# Sheet1.net
KiCad netlist of a schematic drawn in Altium Designer
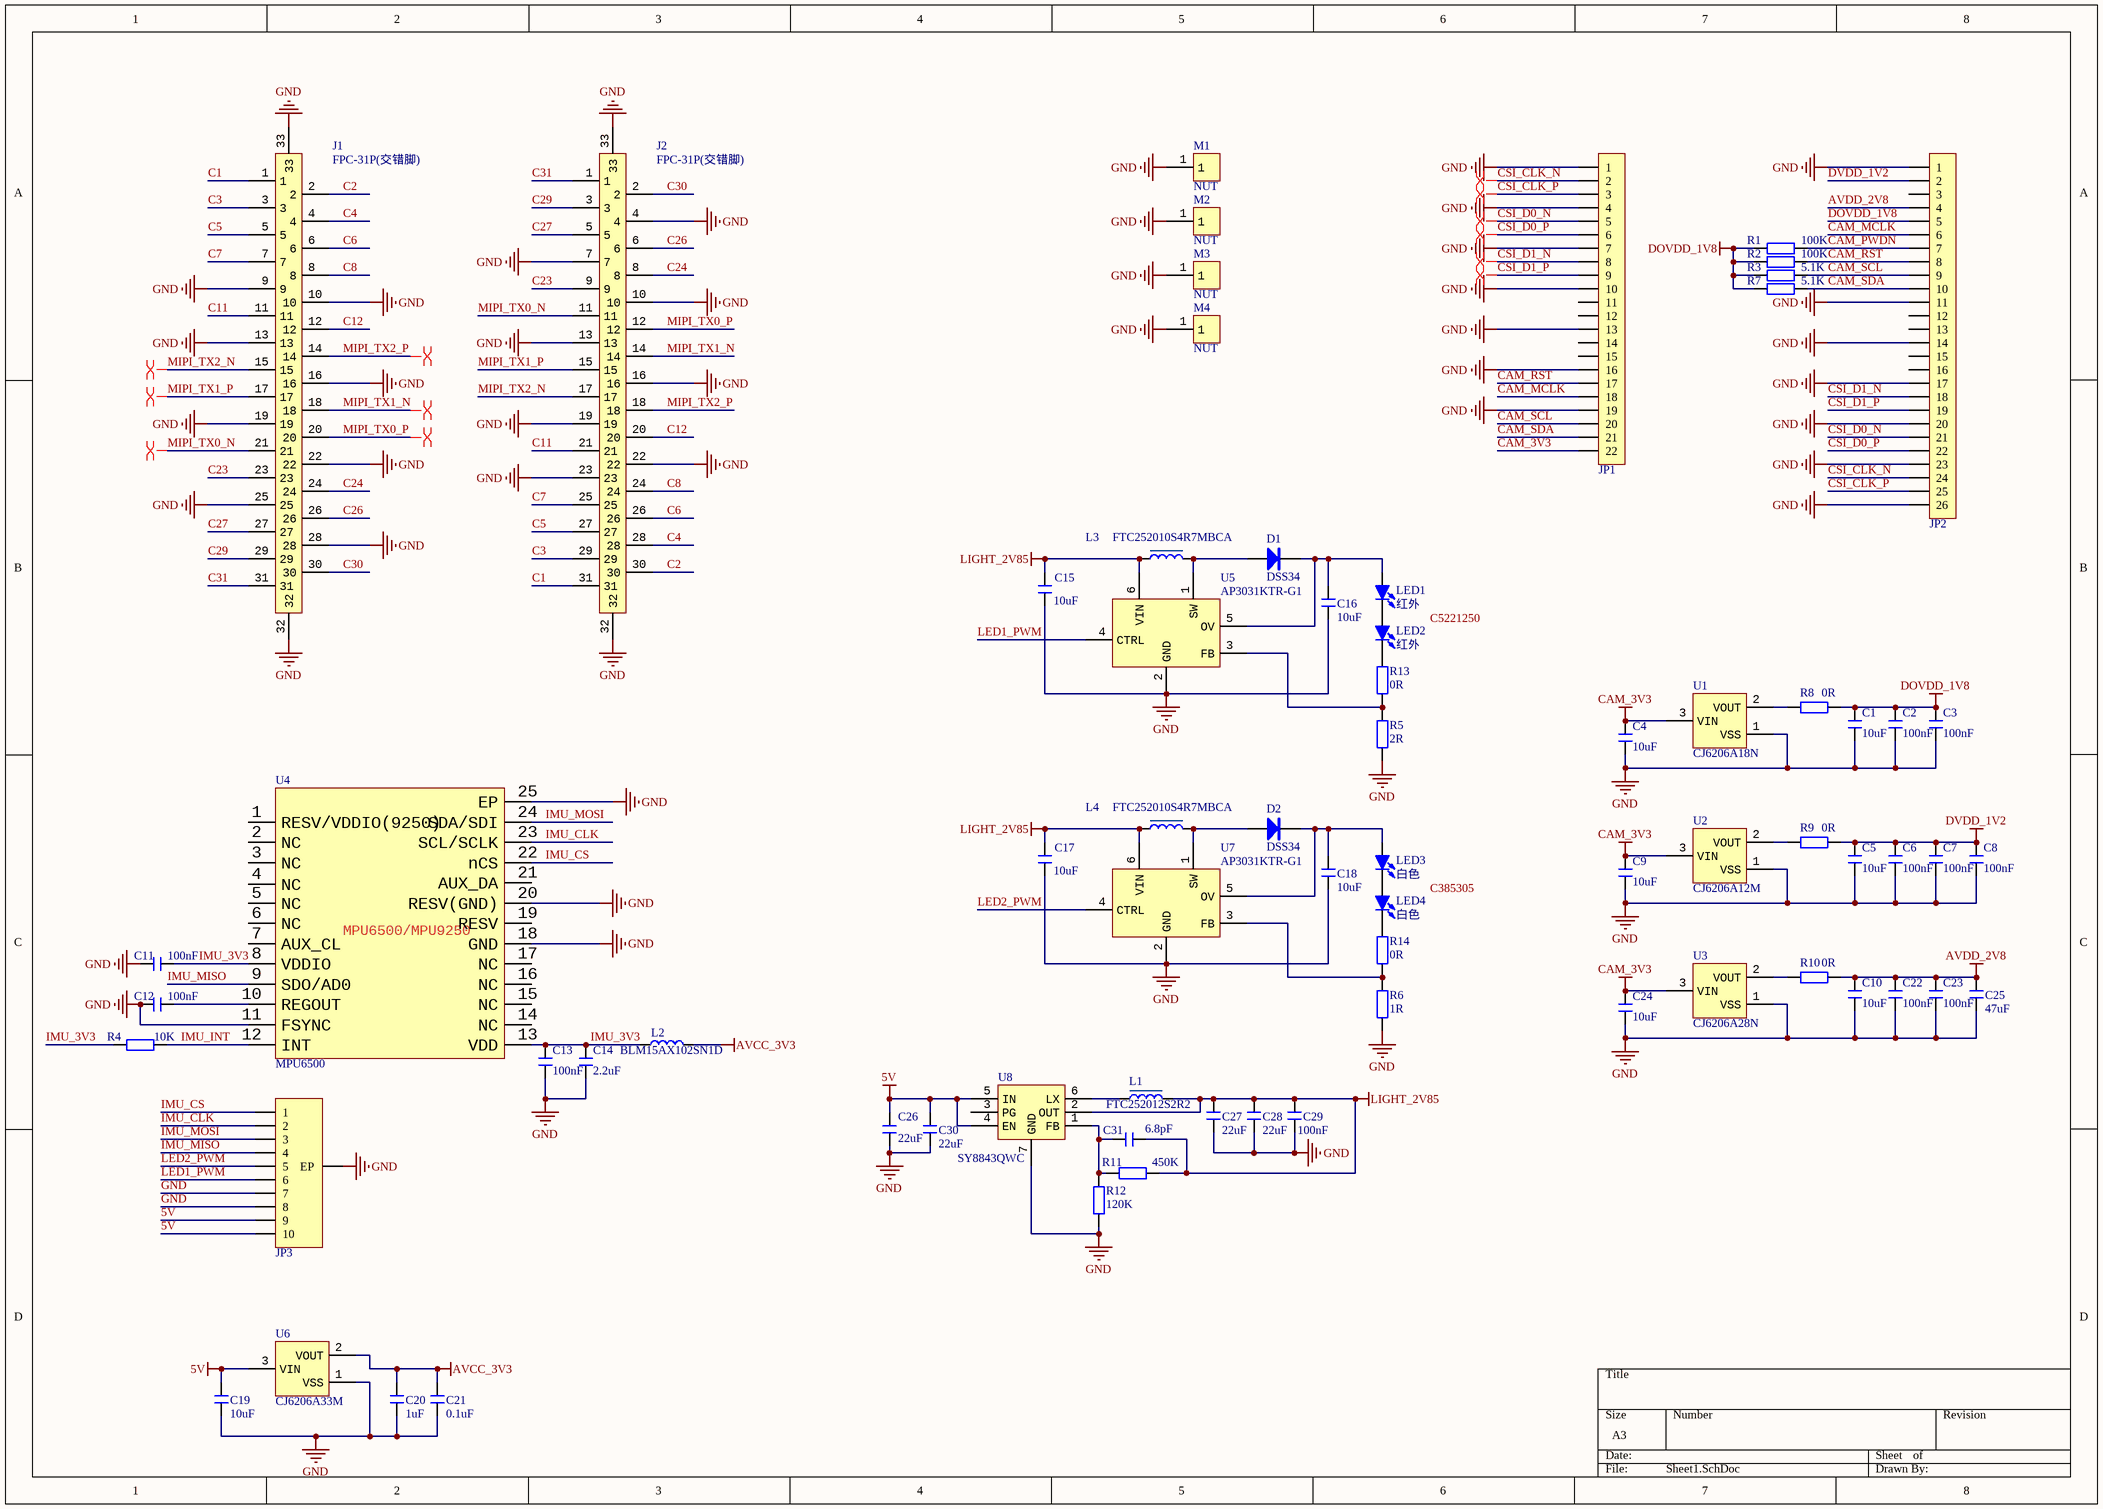
[diagram p0: Sheet1.SchDoc]

(export (version "E")
  (design (tool "Eeschema 10.0.6"))
  (components
    (comp (ref "C1")
      (value "10uF")
      (footprint "C 0402_L")
      (description "无极性贴片电容")
      (fields (field (name "版权归属") "源创客"))
      (libsource (lib "3.1   - 电阻-电容-电感") (part "C"))
    )
    (comp (ref "C2")
      (value "100nF")
      (footprint "C 0402_L")
      (description "无极性贴片电容")
      (fields (field (name "版权归属") "源创客"))
      (libsource (lib "3.1   - 电阻-电容-电感") (part "C"))
    )
    (comp (ref "C3")
      (value "100nF")
      (footprint "C 0402_L")
      (description "无极性贴片电容")
      (fields (field (name "版权归属") "源创客"))
      (libsource (lib "3.1   - 电阻-电容-电感") (part "C"))
    )
    (comp (ref "C4")
      (value "10uF")
      (footprint "C 0402_L")
      (description "无极性贴片电容")
      (fields (field (name "版权归属") "源创客"))
      (libsource (lib "3.1   - 电阻-电容-电感") (part "C"))
    )
    (comp (ref "C5")
      (value "10uF")
      (footprint "C 0402_L")
      (description "无极性贴片电容")
      (fields (field (name "版权归属") "源创客"))
      (libsource (lib "3.1   - 电阻-电容-电感") (part "C"))
    )
    (comp (ref "C6")
      (value "100nF")
      (footprint "C 0402_L")
      (description "无极性贴片电容")
      (fields (field (name "版权归属") "源创客"))
      (libsource (lib "3.1   - 电阻-电容-电感") (part "C"))
    )
    (comp (ref "C7")
      (value "100nF")
      (footprint "C 0402_L")
      (description "无极性贴片电容")
      (fields (field (name "版权归属") "源创客"))
      (libsource (lib "3.1   - 电阻-电容-电感") (part "C"))
    )
    (comp (ref "C8")
      (value "100nF")
      (footprint "C 0402_L")
      (description "无极性贴片电容")
      (fields (field (name "版权归属") "源创客"))
      (libsource (lib "3.1   - 电阻-电容-电感") (part "C"))
    )
    (comp (ref "C9")
      (value "10uF")
      (footprint "C 0402_L")
      (description "无极性贴片电容")
      (fields (field (name "版权归属") "源创客"))
      (libsource (lib "3.1   - 电阻-电容-电感") (part "C"))
    )
    (comp (ref "C10")
      (value "10uF")
      (footprint "C 0402_L")
      (description "无极性贴片电容")
      (fields (field (name "版权归属") "源创客"))
      (libsource (lib "3.1   - 电阻-电容-电感") (part "C"))
    )
    (comp (ref "C11")
      (value "100nF")
      (footprint "C 0402_L")
      (description "无极性贴片电容")
      (fields (field (name "版权归属") "源创客"))
      (libsource (lib "3.1   - 电阻-电容-电感") (part "C"))
    )
    (comp (ref "C12")
      (value "100nF")
      (footprint "C 0402_L")
      (description "无极性贴片电容")
      (fields (field (name "版权归属") "源创客"))
      (libsource (lib "3.1   - 电阻-电容-电感") (part "C"))
    )
    (comp (ref "C13")
      (value "100nF")
      (footprint "C 0402_L")
      (description "无极性贴片电容")
      (fields (field (name "版权归属") "源创客"))
      (libsource (lib "3.1   - 电阻-电容-电感") (part "C"))
    )
    (comp (ref "C14")
      (value "2.2uF")
      (footprint "C 0402_L")
      (description "无极性贴片电容")
      (fields (field (name "版权归属") "源创客"))
      (libsource (lib "3.1   - 电阻-电容-电感") (part "C"))
    )
    (comp (ref "C15")
      (value "10uF")
      (footprint "C 0603_L")
      (description "无极性贴片电容")
      (fields (field (name "版权归属") "源创客"))
      (libsource (lib "3.1   - 电阻-电容-电感") (part "C"))
    )
    (comp (ref "C16")
      (value "10uF")
      (footprint "C 0603_L")
      (description "无极性贴片电容")
      (fields (field (name "版权归属") "源创客"))
      (libsource (lib "3.1   - 电阻-电容-电感") (part "C"))
    )
    (comp (ref "C17")
      (value "10uF")
      (footprint "C 0603_L")
      (description "无极性贴片电容")
      (fields (field (name "版权归属") "源创客"))
      (libsource (lib "3.1   - 电阻-电容-电感") (part "C"))
    )
    (comp (ref "C18")
      (value "10uF")
      (footprint "C 0603_L")
      (description "无极性贴片电容")
      (fields (field (name "版权归属") "源创客"))
      (libsource (lib "3.1   - 电阻-电容-电感") (part "C"))
    )
    (comp (ref "C19")
      (value "10uF")
      (footprint "C 0603_L")
      (description "无极性贴片电容")
      (fields (field (name "版权归属") "源创客"))
      (libsource (lib "3.1   - 电阻-电容-电感") (part "C"))
    )
    (comp (ref "C20")
      (value "1uF")
      (footprint "C 0402_L")
      (description "无极性贴片电容")
      (fields (field (name "版权归属") "源创客"))
      (libsource (lib "3.1   - 电阻-电容-电感") (part "C"))
    )
    (comp (ref "C21")
      (value "0.1uF")
      (footprint "C 0402_L")
      (description "无极性贴片电容")
      (fields (field (name "版权归属") "源创客"))
      (libsource (lib "3.1   - 电阻-电容-电感") (part "C"))
    )
    (comp (ref "C22")
      (value "100nF")
      (footprint "C 0402_L")
      (description "无极性贴片电容")
      (fields (field (name "版权归属") "源创客"))
      (libsource (lib "3.1   - 电阻-电容-电感") (part "C"))
    )
    (comp (ref "C23")
      (value "100nF")
      (footprint "C 0402_L")
      (description "无极性贴片电容")
      (fields (field (name "版权归属") "源创客"))
      (libsource (lib "3.1   - 电阻-电容-电感") (part "C"))
    )
    (comp (ref "C24")
      (value "10uF")
      (footprint "C 0402_L")
      (description "无极性贴片电容")
      (fields (field (name "版权归属") "源创客"))
      (libsource (lib "3.1   - 电阻-电容-电感") (part "C"))
    )
    (comp (ref "C25")
      (value "47uF")
      (footprint "C 0603_L")
      (description "无极性贴片电容")
      (fields (field (name "版权归属") "源创客"))
      (libsource (lib "3.1   - 电阻-电容-电感") (part "C"))
    )
    (comp (ref "C26")
      (value "22uF")
      (footprint "C 0603_L")
      (description "无极性贴片电容")
      (fields (field (name "版权归属") "源创客"))
      (libsource (lib "3.1   - 电阻-电容-电感") (part "C"))
    )
    (comp (ref "C27")
      (value "22uF")
      (footprint "C 0603_L")
      (description "无极性贴片电容")
      (fields (field (name "版权归属") "源创客"))
      (libsource (lib "3.1   - 电阻-电容-电感") (part "C"))
    )
    (comp (ref "C28")
      (value "22uF")
      (footprint "C 0603_L")
      (description "无极性贴片电容")
      (fields (field (name "版权归属") "源创客"))
      (libsource (lib "3.1   - 电阻-电容-电感") (part "C"))
    )
    (comp (ref "C29")
      (value "100nF")
      (footprint "C 0402_L")
      (description "无极性贴片电容")
      (fields (field (name "版权归属") "源创客"))
      (libsource (lib "3.1   - 电阻-电容-电感") (part "C"))
    )
    (comp (ref "C30")
      (value "22uF")
      (footprint "C 0603_L")
      (description "无极性贴片电容")
      (fields (field (name "版权归属") "源创客"))
      (libsource (lib "3.1   - 电阻-电容-电感") (part "C"))
    )
    (comp (ref "C31")
      (value "6.8pF")
      (footprint "C 0402_L")
      (description "无极性贴片电容")
      (fields (field (name "版权归属") "源创客"))
      (libsource (lib "3.1   - 电阻-电容-电感") (part "C"))
    )
    (comp (ref "D1")
      (value "DSS34")
      (footprint "SOD-123FL")
      (description "肖特基二极管")
      (libsource (lib "8.1   - 二极管-整流桥") (part "DSS34"))
    )
    (comp (ref "D2")
      (value "DSS34")
      (footprint "SOD-123FL")
      (description "肖特基二极管")
      (libsource (lib "8.1   - 二极管-整流桥") (part "DSS34"))
    )
    (comp (ref "J1")
      (value "FPC-31P(交错脚)")
      (footprint "FPC 1H-WS-31P")
      (description "FPC连接器")
      (libsource (lib "4.14 - FPC连接器") (part "FPC-31P(交错脚)"))
    )
    (comp (ref "J2")
      (value "FPC-31P(交错脚)")
      (footprint "FPC 1H-WS-31P")
      (description "FPC连接器")
      (libsource (lib "4.14 - FPC连接器") (part "FPC-31P(交错脚)"))
    )
    (comp (ref "JP1")
      (value "FPC1.0-22P")
      (footprint "FPC0.5 2H-WS-22P")
      (description "FPC连接器")
      (fields (field (name "版权归属") "源创客"))
      (libsource (lib "4.14 - FPC连接器") (part "FPC-22P"))
    )
    (comp (ref "JP2")
      (value "FPC1.0-26P")
      (footprint "FPC0.5 2H-WS-26P")
      (description "FPC连接器")
      (fields (field (name "版权归属") "源创客"))
      (libsource (lib "4.14 - FPC连接器") (part "FPC-26P"))
    )
    (comp (ref "JP3")
      (value "FPC1.0-10P")
      (footprint "FPC0.5 1H-WS-10P")
      (description "FPC连接器")
      (fields (field (name "版权归属") "源创客"))
      (libsource (lib "4.14 - FPC连接器") (part "FPC-10P"))
    )
    (comp (ref "L1")
      (value "FTC252012S2R2")
      (footprint "252012")
      (description "贴片功率电感")
      (fields (field (name "版权归属") "源创客"))
      (libsource (lib "3.1   - 电阻-电容-电感") (part "L-CD"))
    )
    (comp (ref "L2")
      (value "BLM15AX102SN1D")
      (footprint "L 0402")
      (description "小功率贴片电感")
      (fields (field (name "版权归属") "源创客"))
      (libsource (lib "3.1   - 电阻-电容-电感") (part "L"))
    )
    (comp (ref "L3")
      (value "FTC252010S4R7MBCA")
      (footprint "252012")
      (description "贴片功率电感")
      (fields (field (name "版权归属") "源创客"))
      (libsource (lib "3.1   - 电阻-电容-电感") (part "L-CD"))
    )
    (comp (ref "L4")
      (value "FTC252010S4R7MBCA")
      (footprint "252012")
      (description "贴片功率电感")
      (fields (field (name "版权归属") "源创客"))
      (libsource (lib "3.1   - 电阻-电容-电感") (part "L-CD"))
    )
    (comp (ref "LED1")
      (value "红外")
      (footprint "LED 3528-2Pin")
      (description "贴片LED")
      (fields (field (name "版权归属") "源创客"))
      (libsource (lib "9.1   - LED") (part "LED-SMD"))
    )
    (comp (ref "LED2")
      (value "红外")
      (footprint "LED 3528-2Pin")
      (description "贴片LED")
      (fields (field (name "版权归属") "源创客"))
      (libsource (lib "9.1   - LED") (part "LED-SMD"))
    )
    (comp (ref "LED3")
      (value "白色")
      (footprint "LED 3528-2Pin")
      (description "贴片LED")
      (fields (field (name "版权归属") "源创客"))
      (libsource (lib "9.1   - LED") (part "LED-SMD"))
    )
    (comp (ref "LED4")
      (value "白色")
      (footprint "LED 3528-2Pin")
      (description "贴片LED")
      (fields (field (name "版权归属") "源创客"))
      (libsource (lib "9.1   - LED") (part "LED-SMD"))
    )
    (comp (ref "M1")
      (value "NUT")
      (footprint "SMT-NUT-M1610")
      (description "SMT表贴螺母")
      (libsource (lib "15.1 - 未分类器件") (part "SMTNUT"))
    )
    (comp (ref "M2")
      (value "NUT")
      (footprint "SMT-NUT-M1610")
      (description "SMT表贴螺母")
      (libsource (lib "15.1 - 未分类器件") (part "SMTNUT"))
    )
    (comp (ref "M3")
      (value "NUT")
      (footprint "SMT-NUT-M1610")
      (description "SMT表贴螺母")
      (libsource (lib "15.1 - 未分类器件") (part "SMTNUT"))
    )
    (comp (ref "M4")
      (value "NUT")
      (footprint "SMT-NUT-M1610")
      (description "SMT表贴螺母")
      (libsource (lib "15.1 - 未分类器件") (part "SMTNUT"))
    )
    (comp (ref "R1")
      (value "100K")
      (footprint "R 0402_L")
      (description "贴片电阻")
      (fields (field (name "版权归属") "源创客"))
      (libsource (lib "3.1   - 电阻-电容-电感") (part "R"))
    )
    (comp (ref "R2")
      (value "100K")
      (footprint "R 0402_L")
      (description "贴片电阻")
      (fields (field (name "版权归属") "源创客"))
      (libsource (lib "3.1   - 电阻-电容-电感") (part "R"))
    )
    (comp (ref "R3")
      (value "5.1K")
      (footprint "R 0402_L")
      (description "贴片电阻")
      (fields (field (name "版权归属") "源创客"))
      (libsource (lib "3.1   - 电阻-电容-电感") (part "R"))
    )
    (comp (ref "R4")
      (value "10K")
      (footprint "R 0402_L")
      (description "贴片电阻")
      (fields (field (name "版权归属") "源创客"))
      (libsource (lib "3.1   - 电阻-电容-电感") (part "R"))
    )
    (comp (ref "R5")
      (value "2R")
      (footprint "R 0603_L")
      (description "贴片电阻")
      (fields (field (name "版权归属") "源创客"))
      (libsource (lib "3.1   - 电阻-电容-电感") (part "R"))
    )
    (comp (ref "R6")
      (value "1R")
      (footprint "R 0603_L")
      (description "贴片电阻")
      (fields (field (name "版权归属") "源创客"))
      (libsource (lib "3.1   - 电阻-电容-电感") (part "R"))
    )
    (comp (ref "R7")
      (value "5.1K")
      (footprint "R 0402_L")
      (description "贴片电阻")
      (fields (field (name "版权归属") "源创客"))
      (libsource (lib "3.1   - 电阻-电容-电感") (part "R"))
    )
    (comp (ref "R8")
      (value "0R")
      (footprint "R 0402_L")
      (description "贴片电阻")
      (fields (field (name "版权归属") "源创客"))
      (libsource (lib "3.1   - 电阻-电容-电感") (part "R"))
    )
    (comp (ref "R9")
      (value "0R")
      (footprint "R 0402_L")
      (description "贴片电阻")
      (fields (field (name "版权归属") "源创客"))
      (libsource (lib "3.1   - 电阻-电容-电感") (part "R"))
    )
    (comp (ref "R10")
      (value "0R")
      (footprint "R 0402_L")
      (description "贴片电阻")
      (fields (field (name "版权归属") "源创客"))
      (libsource (lib "3.1   - 电阻-电容-电感") (part "R"))
    )
    (comp (ref "R11")
      (value "450K")
      (footprint "R 0402_L")
      (description "贴片电阻")
      (fields (field (name "版权归属") "源创客"))
      (libsource (lib "3.1   - 电阻-电容-电感") (part "R"))
    )
    (comp (ref "R12")
      (value "120K")
      (footprint "R 0402_L")
      (description "贴片电阻")
      (fields (field (name "版权归属") "源创客"))
      (libsource (lib "3.1   - 电阻-电容-电感") (part "R"))
    )
    (comp (ref "R13")
      (value "0R")
      (footprint "R 0603_L")
      (description "贴片电阻")
      (fields (field (name "版权归属") "源创客"))
      (libsource (lib "3.1   - 电阻-电容-电感") (part "R"))
    )
    (comp (ref "R14")
      (value "0R")
      (footprint "R 0603_L")
      (description "贴片电阻")
      (fields (field (name "版权归属") "源创客"))
      (libsource (lib "3.1   - 电阻-电容-电感") (part "R"))
    )
    (comp (ref "U1")
      (value "CJ6206A18N")
      (footprint "SOT23-3L")
      (description "三端稳压芯片\r\n6V 250mA")
      (libsource (lib "1.3   - 电源类芯片") (part "LN6206PXXX"))
    )
    (comp (ref "U2")
      (value "CJ6206A12M")
      (footprint "SOT23-3L")
      (description "三端稳压芯片\r\n6V 250mA")
      (libsource (lib "1.3   - 电源类芯片") (part "LN6206PXXX"))
    )
    (comp (ref "U3")
      (value "CJ6206A28N")
      (footprint "SOT23-3L")
      (description "三端稳压芯片\r\n6V 250mA")
      (libsource (lib "1.3   - 电源类芯片") (part "LN6206PXXX"))
    )
    (comp (ref "U4")
      (value "MPU6500")
      (footprint "QFN24 3X3")
      (description "6轴IMU")
      (libsource (lib "11.1 - 传感元件") (part "MPU6500"))
    )
    (comp (ref "U5")
      (value "AP3031KTR-G1")
      (footprint "SOT23-6L")
      (description "LED驱动")
      (libsource (lib "1.1   - IC芯片") (part "AP3031"))
    )
    (comp (ref "U6")
      (value "CJ6206A33M")
      (footprint "SOT23-3L")
      (description "三端稳压芯片\r\n6V 250mA")
      (libsource (lib "1.3   - 电源类芯片") (part "LN6206PXXX"))
    )
    (comp (ref "U7")
      (value "AP3031KTR-G1")
      (footprint "SOT23-6L")
      (description "LED驱动")
      (libsource (lib "1.1   - IC芯片") (part "AP3031"))
    )
    (comp (ref "U8")
      (value "SY8843QWC")
      (footprint "QFN7 1.5X1.5")
      (description "DC-DC 1.5M\r\nVIN:2.7~5.5V 3A")
      (libsource (lib "1.3   - 电源类芯片") (part "SY8843QWC"))
    )
  )
  (nets
    (net (code "1") (name "/C1") (class "Default")
      (node (ref "J1") (pin "1") (pinfunction "1_1") (pintype "passive"))
      (node (ref "J2") (pin "31") (pinfunction "31_31") (pintype "passive"))
    )
    (net (code "2") (name "/C2") (class "Default")
      (node (ref "J1") (pin "2") (pinfunction "2_2") (pintype "passive"))
      (node (ref "J2") (pin "30") (pinfunction "30_30") (pintype "passive"))
    )
    (net (code "3") (name "/C3") (class "Default")
      (node (ref "J1") (pin "3") (pinfunction "3_3") (pintype "passive"))
      (node (ref "J2") (pin "29") (pinfunction "29_29") (pintype "passive"))
    )
    (net (code "4") (name "/C4") (class "Default")
      (node (ref "J1") (pin "4") (pinfunction "4_4") (pintype "passive"))
      (node (ref "J2") (pin "28") (pinfunction "28_28") (pintype "passive"))
    )
    (net (code "5") (name "/C5") (class "Default")
      (node (ref "J1") (pin "5") (pinfunction "5_5") (pintype "passive"))
      (node (ref "J2") (pin "27") (pinfunction "27_27") (pintype "passive"))
    )
    (net (code "6") (name "/C6") (class "Default")
      (node (ref "J1") (pin "6") (pinfunction "6_6") (pintype "passive"))
      (node (ref "J2") (pin "26") (pinfunction "26_26") (pintype "passive"))
    )
    (net (code "7") (name "/C7") (class "Default")
      (node (ref "J1") (pin "7") (pinfunction "7_7") (pintype "passive"))
      (node (ref "J2") (pin "25") (pinfunction "25_25") (pintype "passive"))
    )
    (net (code "8") (name "/C8") (class "Default")
      (node (ref "J1") (pin "8") (pinfunction "8_8") (pintype "passive"))
      (node (ref "J2") (pin "24") (pinfunction "24_24") (pintype "passive"))
    )
    (net (code "9") (name "/C11") (class "Default")
      (node (ref "J1") (pin "11") (pinfunction "11_11") (pintype "passive"))
      (node (ref "J2") (pin "21") (pinfunction "21_21") (pintype "passive"))
    )
    (net (code "10") (name "/C12") (class "Default")
      (node (ref "J1") (pin "12") (pinfunction "12_12") (pintype "passive"))
      (node (ref "J2") (pin "20") (pinfunction "20_20") (pintype "passive"))
    )
    (net (code "11") (name "/C23") (class "Default")
      (node (ref "J1") (pin "23") (pinfunction "23_23") (pintype "passive"))
      (node (ref "J2") (pin "9") (pinfunction "9_9") (pintype "passive"))
    )
    (net (code "12") (name "/C24") (class "Default")
      (node (ref "J1") (pin "24") (pinfunction "24_24") (pintype "passive"))
      (node (ref "J2") (pin "8") (pinfunction "8_8") (pintype "passive"))
    )
    (net (code "13") (name "/C26") (class "Default")
      (node (ref "J1") (pin "26") (pinfunction "26_26") (pintype "passive"))
      (node (ref "J2") (pin "6") (pinfunction "6_6") (pintype "passive"))
    )
    (net (code "14") (name "/C27") (class "Default")
      (node (ref "J1") (pin "27") (pinfunction "27_27") (pintype "passive"))
      (node (ref "J2") (pin "5") (pinfunction "5_5") (pintype "passive"))
    )
    (net (code "15") (name "/C29") (class "Default")
      (node (ref "J1") (pin "29") (pinfunction "29_29") (pintype "passive"))
      (node (ref "J2") (pin "3") (pinfunction "3_3") (pintype "passive"))
    )
    (net (code "16") (name "/C30") (class "Default")
      (node (ref "J1") (pin "30") (pinfunction "30_30") (pintype "passive"))
      (node (ref "J2") (pin "2") (pinfunction "2_2") (pintype "passive"))
    )
    (net (code "17") (name "/C31") (class "Default")
      (node (ref "J1") (pin "31") (pinfunction "31_31") (pintype "passive"))
      (node (ref "J2") (pin "1") (pinfunction "1_1") (pintype "passive"))
    )
    (net (code "18") (name "/CAM_MCLK") (class "Default")
      (node (ref "JP1") (pin "18") (pinfunction "18_18") (pintype "passive"))
      (node (ref "JP2") (pin "6") (pinfunction "6_6") (pintype "passive"))
    )
    (net (code "19") (name "/CAM_PWDN") (class "Default")
      (node (ref "JP2") (pin "7") (pinfunction "7_7") (pintype "passive"))
      (node (ref "R1") (pin "2") (pinfunction "2_2") (pintype "passive"))
    )
    (net (code "20") (name "/CAM_RST") (class "Default")
      (node (ref "JP1") (pin "17") (pinfunction "17_17") (pintype "passive"))
      (node (ref "JP2") (pin "8") (pinfunction "8_8") (pintype "passive"))
      (node (ref "R2") (pin "2") (pinfunction "2_2") (pintype "passive"))
    )
    (net (code "21") (name "/CAM_SCL") (class "Default")
      (node (ref "JP1") (pin "20") (pinfunction "20_20") (pintype "passive"))
      (node (ref "JP2") (pin "9") (pinfunction "9_9") (pintype "passive"))
      (node (ref "R3") (pin "2") (pinfunction "2_2") (pintype "passive"))
    )
    (net (code "22") (name "/CAM_SDA") (class "Default")
      (node (ref "JP1") (pin "21") (pinfunction "21_21") (pintype "passive"))
      (node (ref "JP2") (pin "10") (pinfunction "10_10") (pintype "passive"))
      (node (ref "R7") (pin "2") (pinfunction "2_2") (pintype "passive"))
    )
    (net (code "23") (name "/CSI_CLK_N") (class "Default")
      (node (ref "JP1") (pin "2") (pinfunction "2_2") (pintype "passive"))
      (node (ref "JP2") (pin "24") (pinfunction "24_24") (pintype "passive"))
    )
    (net (code "24") (name "/CSI_CLK_P") (class "Default")
      (node (ref "JP1") (pin "3") (pinfunction "3_3") (pintype "passive"))
      (node (ref "JP2") (pin "25") (pinfunction "25_25") (pintype "passive"))
    )
    (net (code "25") (name "/CSI_D0_N") (class "Default")
      (node (ref "JP1") (pin "5") (pinfunction "5_5") (pintype "passive"))
      (node (ref "JP2") (pin "21") (pinfunction "21_21") (pintype "passive"))
    )
    (net (code "26") (name "/CSI_D0_P") (class "Default")
      (node (ref "JP1") (pin "6") (pinfunction "6_6") (pintype "passive"))
      (node (ref "JP2") (pin "22") (pinfunction "22_22") (pintype "passive"))
    )
    (net (code "27") (name "/CSI_D1_N") (class "Default")
      (node (ref "JP1") (pin "8") (pinfunction "8_8") (pintype "passive"))
      (node (ref "JP2") (pin "18") (pinfunction "18_18") (pintype "passive"))
    )
    (net (code "28") (name "/CSI_D1_P") (class "Default")
      (node (ref "JP1") (pin "9") (pinfunction "9_9") (pintype "passive"))
      (node (ref "JP2") (pin "19") (pinfunction "19_19") (pintype "passive"))
    )
    (net (code "29") (name "/IMU_3V3") (class "Default")
      (node (ref "C11") (pin "1") (pinfunction "1_1") (pintype "passive"))
      (node (ref "C13") (pin "2") (pinfunction "2_2") (pintype "passive"))
      (node (ref "C14") (pin "2") (pinfunction "2_2") (pintype "passive"))
      (node (ref "L2") (pin "1") (pinfunction "1_1") (pintype "passive"))
      (node (ref "R4") (pin "1") (pinfunction "1_1") (pintype "passive"))
      (node (ref "U4") (pin "13") (pinfunction "VDD_13") (pintype "passive"))
      (node (ref "U4") (pin "8") (pinfunction "VDDIO_8") (pintype "passive"))
    )
    (net (code "30") (name "/IMU_CLK") (class "Default")
      (node (ref "JP3") (pin "2") (pinfunction "2_2") (pintype "passive"))
      (node (ref "U4") (pin "23") (pinfunction "SCL/SCLK_23") (pintype "passive"))
    )
    (net (code "31") (name "/IMU_CS") (class "Default")
      (node (ref "JP3") (pin "1") (pinfunction "1_1") (pintype "passive"))
      (node (ref "U4") (pin "22") (pinfunction "nCS_22") (pintype "passive"))
    )
    (net (code "32") (name "/IMU_INT") (class "Default")
      (node (ref "R4") (pin "2") (pinfunction "2_2") (pintype "passive"))
      (node (ref "U4") (pin "12") (pinfunction "INT_12") (pintype "passive"))
    )
    (net (code "33") (name "/IMU_MISO") (class "Default")
      (node (ref "JP3") (pin "4") (pinfunction "4_4") (pintype "passive"))
      (node (ref "U4") (pin "9") (pinfunction "SDO/AD0_9") (pintype "passive"))
    )
    (net (code "34") (name "/IMU_MOSI") (class "Default")
      (node (ref "JP3") (pin "3") (pinfunction "3_3") (pintype "passive"))
      (node (ref "U4") (pin "24") (pinfunction "SDA/SDI_24") (pintype "passive"))
    )
    (net (code "35") (name "/LED1_PWM") (class "Default")
      (node (ref "JP3") (pin "6") (pinfunction "6_6") (pintype "passive"))
      (node (ref "U5") (pin "4") (pinfunction "CTRL_4") (pintype "passive"))
    )
    (net (code "36") (name "/LED2_PWM") (class "Default")
      (node (ref "JP3") (pin "5") (pinfunction "5_5") (pintype "passive"))
      (node (ref "U7") (pin "4") (pinfunction "CTRL_4") (pintype "passive"))
    )
    (net (code "37") (name "/MIPI_TX0_N") (class "Default")
      (node (ref "J1") (pin "21") (pinfunction "21_21") (pintype "passive"))
      (node (ref "J2") (pin "11") (pinfunction "11_11") (pintype "passive"))
    )
    (net (code "38") (name "/MIPI_TX0_P") (class "Default")
      (node (ref "J1") (pin "20") (pinfunction "20_20") (pintype "passive"))
      (node (ref "J2") (pin "12") (pinfunction "12_12") (pintype "passive"))
    )
    (net (code "39") (name "/MIPI_TX1_N") (class "Default")
      (node (ref "J1") (pin "18") (pinfunction "18_18") (pintype "passive"))
      (node (ref "J2") (pin "14") (pinfunction "14_14") (pintype "passive"))
    )
    (net (code "40") (name "/MIPI_TX1_P") (class "Default")
      (node (ref "J1") (pin "17") (pinfunction "17_17") (pintype "passive"))
      (node (ref "J2") (pin "15") (pinfunction "15_15") (pintype "passive"))
    )
    (net (code "41") (name "/MIPI_TX2_N") (class "Default")
      (node (ref "J1") (pin "15") (pinfunction "15_15") (pintype "passive"))
      (node (ref "J2") (pin "17") (pinfunction "17_17") (pintype "passive"))
    )
    (net (code "42") (name "/MIPI_TX2_P") (class "Default")
      (node (ref "J1") (pin "14") (pinfunction "14_14") (pintype "passive"))
      (node (ref "J2") (pin "18") (pinfunction "18_18") (pintype "passive"))
    )
    (net (code "43") (name "5V") (class "Default")
      (node (ref "C19") (pin "2") (pinfunction "2_2") (pintype "passive"))
      (node (ref "C26") (pin "2") (pinfunction "2_2") (pintype "passive"))
      (node (ref "C30") (pin "2") (pinfunction "2_2") (pintype "passive"))
      (node (ref "JP3") (pin "10") (pinfunction "10_10") (pintype "passive"))
      (node (ref "JP3") (pin "9") (pinfunction "9_9") (pintype "passive"))
      (node (ref "U6") (pin "3") (pinfunction "VIN_3") (pintype "passive"))
      (node (ref "U8") (pin "4") (pinfunction "EN_4") (pintype "passive"))
      (node (ref "U8") (pin "5") (pinfunction "IN_5") (pintype "passive"))
    )
    (net (code "44") (name "AVCC_3V3") (class "Default")
      (node (ref "C20") (pin "2") (pinfunction "2_2") (pintype "passive"))
      (node (ref "C21") (pin "2") (pinfunction "2_2") (pintype "passive"))
      (node (ref "L2") (pin "2") (pinfunction "2_2") (pintype "passive"))
      (node (ref "U6") (pin "2") (pinfunction "VOUT_2") (pintype "passive"))
    )
    (net (code "45") (name "AVDD_2V8") (class "Default")
      (node (ref "C10") (pin "2") (pinfunction "2_2") (pintype "passive"))
      (node (ref "C22") (pin "2") (pinfunction "2_2") (pintype "passive"))
      (node (ref "C23") (pin "2") (pinfunction "2_2") (pintype "passive"))
      (node (ref "C25") (pin "2") (pinfunction "2_2") (pintype "passive"))
      (node (ref "JP2") (pin "4") (pinfunction "4_4") (pintype "passive"))
      (node (ref "R10") (pin "2") (pinfunction "2_2") (pintype "passive"))
    )
    (net (code "46") (name "CAM_3V3") (class "Default")
      (node (ref "C24") (pin "2") (pinfunction "2_2") (pintype "passive"))
      (node (ref "C4") (pin "2") (pinfunction "2_2") (pintype "passive"))
      (node (ref "C9") (pin "2") (pinfunction "2_2") (pintype "passive"))
      (node (ref "JP1") (pin "22") (pinfunction "22_22") (pintype "passive"))
      (node (ref "U1") (pin "3") (pinfunction "VIN_3") (pintype "passive"))
      (node (ref "U2") (pin "3") (pinfunction "VIN_3") (pintype "passive"))
      (node (ref "U3") (pin "3") (pinfunction "VIN_3") (pintype "passive"))
    )
    (net (code "47") (name "DOVDD_1V8") (class "Default")
      (node (ref "C1") (pin "2") (pinfunction "2_2") (pintype "passive"))
      (node (ref "C2") (pin "2") (pinfunction "2_2") (pintype "passive"))
      (node (ref "C3") (pin "2") (pinfunction "2_2") (pintype "passive"))
      (node (ref "JP2") (pin "5") (pinfunction "5_5") (pintype "passive"))
      (node (ref "R1") (pin "1") (pinfunction "1_1") (pintype "passive"))
      (node (ref "R2") (pin "1") (pinfunction "1_1") (pintype "passive"))
      (node (ref "R3") (pin "1") (pinfunction "1_1") (pintype "passive"))
      (node (ref "R7") (pin "1") (pinfunction "1_1") (pintype "passive"))
      (node (ref "R8") (pin "2") (pinfunction "2_2") (pintype "passive"))
    )
    (net (code "48") (name "DVDD_1V2") (class "Default")
      (node (ref "C5") (pin "2") (pinfunction "2_2") (pintype "passive"))
      (node (ref "C6") (pin "2") (pinfunction "2_2") (pintype "passive"))
      (node (ref "C7") (pin "2") (pinfunction "2_2") (pintype "passive"))
      (node (ref "C8") (pin "2") (pinfunction "2_2") (pintype "passive"))
      (node (ref "JP2") (pin "2") (pinfunction "2_2") (pintype "passive"))
      (node (ref "R9") (pin "2") (pinfunction "2_2") (pintype "passive"))
    )
    (net (code "49") (name "GND") (class "Default")
      (node (ref "C1") (pin "1") (pinfunction "1_1") (pintype "passive"))
      (node (ref "C10") (pin "1") (pinfunction "1_1") (pintype "passive"))
      (node (ref "C11") (pin "2") (pinfunction "2_2") (pintype "passive"))
      (node (ref "C12") (pin "2") (pinfunction "2_2") (pintype "passive"))
      (node (ref "C13") (pin "1") (pinfunction "1_1") (pintype "passive"))
      (node (ref "C14") (pin "1") (pinfunction "1_1") (pintype "passive"))
      (node (ref "C15") (pin "1") (pinfunction "1_1") (pintype "passive"))
      (node (ref "C16") (pin "1") (pinfunction "1_1") (pintype "passive"))
      (node (ref "C17") (pin "1") (pinfunction "1_1") (pintype "passive"))
      (node (ref "C18") (pin "1") (pinfunction "1_1") (pintype "passive"))
      (node (ref "C19") (pin "1") (pinfunction "1_1") (pintype "passive"))
      (node (ref "C2") (pin "1") (pinfunction "1_1") (pintype "passive"))
      (node (ref "C20") (pin "1") (pinfunction "1_1") (pintype "passive"))
      (node (ref "C21") (pin "1") (pinfunction "1_1") (pintype "passive"))
      (node (ref "C22") (pin "1") (pinfunction "1_1") (pintype "passive"))
      (node (ref "C23") (pin "1") (pinfunction "1_1") (pintype "passive"))
      (node (ref "C24") (pin "1") (pinfunction "1_1") (pintype "passive"))
      (node (ref "C25") (pin "1") (pinfunction "1_1") (pintype "passive"))
      (node (ref "C26") (pin "1") (pinfunction "1_1") (pintype "passive"))
      (node (ref "C27") (pin "1") (pinfunction "1_1") (pintype "passive"))
      (node (ref "C28") (pin "1") (pinfunction "1_1") (pintype "passive"))
      (node (ref "C29") (pin "1") (pinfunction "1_1") (pintype "passive"))
      (node (ref "C3") (pin "1") (pinfunction "1_1") (pintype "passive"))
      (node (ref "C30") (pin "1") (pinfunction "1_1") (pintype "passive"))
      (node (ref "C4") (pin "1") (pinfunction "1_1") (pintype "passive"))
      (node (ref "C5") (pin "1") (pinfunction "1_1") (pintype "passive"))
      (node (ref "C6") (pin "1") (pinfunction "1_1") (pintype "passive"))
      (node (ref "C7") (pin "1") (pinfunction "1_1") (pintype "passive"))
      (node (ref "C8") (pin "1") (pinfunction "1_1") (pintype "passive"))
      (node (ref "C9") (pin "1") (pinfunction "1_1") (pintype "passive"))
      (node (ref "J1") (pin "10") (pinfunction "10_10") (pintype "passive"))
      (node (ref "J1") (pin "13") (pinfunction "13_13") (pintype "passive"))
      (node (ref "J1") (pin "16") (pinfunction "16_16") (pintype "passive"))
      (node (ref "J1") (pin "19") (pinfunction "19_19") (pintype "passive"))
      (node (ref "J1") (pin "22") (pinfunction "22_22") (pintype "passive"))
      (node (ref "J1") (pin "25") (pinfunction "25_25") (pintype "passive"))
      (node (ref "J1") (pin "28") (pinfunction "28_28") (pintype "passive"))
      (node (ref "J1") (pin "32") (pinfunction "32_32") (pintype "passive"))
      (node (ref "J1") (pin "33") (pinfunction "33_33") (pintype "passive"))
      (node (ref "J1") (pin "9") (pinfunction "9_9") (pintype "passive"))
      (node (ref "J2") (pin "10") (pinfunction "10_10") (pintype "passive"))
      (node (ref "J2") (pin "13") (pinfunction "13_13") (pintype "passive"))
      (node (ref "J2") (pin "16") (pinfunction "16_16") (pintype "passive"))
      (node (ref "J2") (pin "19") (pinfunction "19_19") (pintype "passive"))
      (node (ref "J2") (pin "22") (pinfunction "22_22") (pintype "passive"))
      (node (ref "J2") (pin "23") (pinfunction "23_23") (pintype "passive"))
      (node (ref "J2") (pin "32") (pinfunction "32_32") (pintype "passive"))
      (node (ref "J2") (pin "33") (pinfunction "33_33") (pintype "passive"))
      (node (ref "J2") (pin "4") (pinfunction "4_4") (pintype "passive"))
      (node (ref "J2") (pin "7") (pinfunction "7_7") (pintype "passive"))
      (node (ref "JP1") (pin "1") (pinfunction "1_1") (pintype "passive"))
      (node (ref "JP1") (pin "10") (pinfunction "10_10") (pintype "passive"))
      (node (ref "JP1") (pin "13") (pinfunction "13_13") (pintype "passive"))
      (node (ref "JP1") (pin "16") (pinfunction "16_16") (pintype "passive"))
      (node (ref "JP1") (pin "19") (pinfunction "19_19") (pintype "passive"))
      (node (ref "JP1") (pin "4") (pinfunction "4_4") (pintype "passive"))
      (node (ref "JP1") (pin "7") (pinfunction "7_7") (pintype "passive"))
      (node (ref "JP2") (pin "1") (pinfunction "1_1") (pintype "passive"))
      (node (ref "JP2") (pin "11") (pinfunction "11_11") (pintype "passive"))
      (node (ref "JP2") (pin "14") (pinfunction "14_14") (pintype "passive"))
      (node (ref "JP2") (pin "17") (pinfunction "17_17") (pintype "passive"))
      (node (ref "JP2") (pin "20") (pinfunction "20_20") (pintype "passive"))
      (node (ref "JP2") (pin "23") (pinfunction "23_23") (pintype "passive"))
      (node (ref "JP2") (pin "26") (pinfunction "26_26") (pintype "passive"))
      (node (ref "JP3") (pin "0") (pinfunction "EP_0") (pintype "passive"))
      (node (ref "JP3") (pin "7") (pinfunction "7_7") (pintype "passive"))
      (node (ref "JP3") (pin "8") (pinfunction "8_8") (pintype "passive"))
      (node (ref "M1") (pin "1") (pinfunction "1_1") (pintype "passive"))
      (node (ref "M2") (pin "1") (pinfunction "1_1") (pintype "passive"))
      (node (ref "M3") (pin "1") (pinfunction "1_1") (pintype "passive"))
      (node (ref "M4") (pin "1") (pinfunction "1_1") (pintype "passive"))
      (node (ref "R12") (pin "2") (pinfunction "2_2") (pintype "passive"))
      (node (ref "R5") (pin "1") (pinfunction "1_1") (pintype "passive"))
      (node (ref "R6") (pin "1") (pinfunction "1_1") (pintype "passive"))
      (node (ref "U1") (pin "1") (pinfunction "VSS_1") (pintype "passive"))
      (node (ref "U2") (pin "1") (pinfunction "VSS_1") (pintype "passive"))
      (node (ref "U3") (pin "1") (pinfunction "VSS_1") (pintype "passive"))
      (node (ref "U4") (pin "11") (pinfunction "FSYNC_11") (pintype "passive"))
      (node (ref "U4") (pin "18") (pinfunction "GND_18") (pintype "passive"))
      (node (ref "U4") (pin "20") (pinfunction "RESV(GND)_20") (pintype "passive"))
      (node (ref "U4") (pin "25") (pinfunction "EP_25") (pintype "passive"))
      (node (ref "U5") (pin "2") (pinfunction "GND_2") (pintype "passive"))
      (node (ref "U6") (pin "1") (pinfunction "VSS_1") (pintype "passive"))
      (node (ref "U7") (pin "2") (pinfunction "GND_2") (pintype "passive"))
      (node (ref "U8") (pin "7") (pinfunction "GND_7") (pintype "passive"))
    )
    (net (code "50") (name "LIGHT_2V85") (class "Default")
      (node (ref "C15") (pin "2") (pinfunction "2_2") (pintype "passive"))
      (node (ref "C17") (pin "2") (pinfunction "2_2") (pintype "passive"))
      (node (ref "C27") (pin "2") (pinfunction "2_2") (pintype "passive"))
      (node (ref "C28") (pin "2") (pinfunction "2_2") (pintype "passive"))
      (node (ref "C29") (pin "2") (pinfunction "2_2") (pintype "passive"))
      (node (ref "C31") (pin "1") (pinfunction "1_1") (pintype "passive"))
      (node (ref "L1") (pin "2") (pinfunction "2_2") (pintype "passive"))
      (node (ref "L3") (pin "1") (pinfunction "1_1") (pintype "passive"))
      (node (ref "L4") (pin "1") (pinfunction "1_1") (pintype "passive"))
      (node (ref "R11") (pin "1") (pinfunction "1_1") (pintype "passive"))
      (node (ref "U5") (pin "6") (pinfunction "VIN_6") (pintype "passive"))
      (node (ref "U7") (pin "6") (pinfunction "VIN_6") (pintype "passive"))
      (node (ref "U8") (pin "2") (pinfunction "OUT_2") (pintype "passive"))
    )
    (net (code "51") (name "Net-(D1-A)") (class "Default")
      (node (ref "D1") (pin "2") (pinfunction "A_2") (pintype "passive"))
      (node (ref "L3") (pin "2") (pinfunction "2_2") (pintype "passive"))
      (node (ref "U5") (pin "1") (pinfunction "SW_1") (pintype "passive"))
    )
    (net (code "52") (name "Net-(D1-K)") (class "Default")
      (node (ref "C16") (pin "2") (pinfunction "2_2") (pintype "passive"))
      (node (ref "D1") (pin "1") (pinfunction "K_1") (pintype "passive"))
      (node (ref "LED1") (pin "2") (pinfunction "A_2") (pintype "passive"))
      (node (ref "U5") (pin "5") (pinfunction "OV_5") (pintype "passive"))
    )
    (net (code "53") (name "Net-(D2-A)") (class "Default")
      (node (ref "D2") (pin "2") (pinfunction "A_2") (pintype "passive"))
      (node (ref "L4") (pin "2") (pinfunction "2_2") (pintype "passive"))
      (node (ref "U7") (pin "1") (pinfunction "SW_1") (pintype "passive"))
    )
    (net (code "54") (name "Net-(D2-K)") (class "Default")
      (node (ref "C18") (pin "2") (pinfunction "2_2") (pintype "passive"))
      (node (ref "D2") (pin "1") (pinfunction "K_1") (pintype "passive"))
      (node (ref "LED3") (pin "2") (pinfunction "A_2") (pintype "passive"))
      (node (ref "U7") (pin "5") (pinfunction "OV_5") (pintype "passive"))
    )
    (net (code "55") (name "Net-(LED1-K)") (class "Default")
      (node (ref "LED1") (pin "1") (pinfunction "K_1") (pintype "passive"))
      (node (ref "LED2") (pin "2") (pinfunction "A_2") (pintype "passive"))
    )
    (net (code "56") (name "Net-(LED2-K)") (class "Default")
      (node (ref "LED2") (pin "1") (pinfunction "K_1") (pintype "passive"))
      (node (ref "R13") (pin "2") (pinfunction "2_2") (pintype "passive"))
    )
    (net (code "57") (name "Net-(LED3-K)") (class "Default")
      (node (ref "LED3") (pin "1") (pinfunction "K_1") (pintype "passive"))
      (node (ref "LED4") (pin "2") (pinfunction "A_2") (pintype "passive"))
    )
    (net (code "58") (name "Net-(LED4-K)") (class "Default")
      (node (ref "LED4") (pin "1") (pinfunction "K_1") (pintype "passive"))
      (node (ref "R14") (pin "2") (pinfunction "2_2") (pintype "passive"))
    )
    (net (code "59") (name "Net-(U1-VOUT)") (class "Default")
      (node (ref "R8") (pin "1") (pinfunction "1_1") (pintype "passive"))
      (node (ref "U1") (pin "2") (pinfunction "VOUT_2") (pintype "passive"))
    )
    (net (code "60") (name "Net-(U2-VOUT)") (class "Default")
      (node (ref "R9") (pin "1") (pinfunction "1_1") (pintype "passive"))
      (node (ref "U2") (pin "2") (pinfunction "VOUT_2") (pintype "passive"))
    )
    (net (code "61") (name "Net-(U3-VOUT)") (class "Default")
      (node (ref "R10") (pin "1") (pinfunction "1_1") (pintype "passive"))
      (node (ref "U3") (pin "2") (pinfunction "VOUT_2") (pintype "passive"))
    )
    (net (code "62") (name "Net-(U4-REGOUT)") (class "Default")
      (node (ref "C12") (pin "1") (pinfunction "1_1") (pintype "passive"))
      (node (ref "U4") (pin "10") (pinfunction "REGOUT_10") (pintype "passive"))
    )
    (net (code "63") (name "Net-(U5-FB)") (class "Default")
      (node (ref "R13") (pin "1") (pinfunction "1_1") (pintype "passive"))
      (node (ref "R5") (pin "2") (pinfunction "2_2") (pintype "passive"))
      (node (ref "U5") (pin "3") (pinfunction "FB_3") (pintype "passive"))
    )
    (net (code "64") (name "Net-(U7-FB)") (class "Default")
      (node (ref "R14") (pin "1") (pinfunction "1_1") (pintype "passive"))
      (node (ref "R6") (pin "2") (pinfunction "2_2") (pintype "passive"))
      (node (ref "U7") (pin "3") (pinfunction "FB_3") (pintype "passive"))
    )
    (net (code "65") (name "Net-(U8-FB)") (class "Default")
      (node (ref "C31") (pin "2") (pinfunction "2_2") (pintype "passive"))
      (node (ref "R11") (pin "2") (pinfunction "2_2") (pintype "passive"))
      (node (ref "R12") (pin "1") (pinfunction "1_1") (pintype "passive"))
      (node (ref "U8") (pin "1") (pinfunction "FB_1") (pintype "passive"))
    )
    (net (code "66") (name "Net-(U8-LX)") (class "Default")
      (node (ref "L1") (pin "1") (pinfunction "1_1") (pintype "passive"))
      (node (ref "U8") (pin "6") (pinfunction "LX_6") (pintype "passive"))
    )
    (net (code "67") (name "unconnected-(JP1-Pad11)") (class "Default")
      (node (ref "JP1") (pin "11") (pinfunction "11_11") (pintype "passive"))
    )
    (net (code "68") (name "unconnected-(JP1-Pad12)") (class "Default")
      (node (ref "JP1") (pin "12") (pinfunction "12_12") (pintype "passive"))
    )
    (net (code "69") (name "unconnected-(JP1-Pad14)") (class "Default")
      (node (ref "JP1") (pin "14") (pinfunction "14_14") (pintype "passive"))
    )
    (net (code "70") (name "unconnected-(JP1-Pad15)") (class "Default")
      (node (ref "JP1") (pin "15") (pinfunction "15_15") (pintype "passive"))
    )
    (net (code "71") (name "unconnected-(JP2-Pad3)") (class "Default")
      (node (ref "JP2") (pin "3") (pinfunction "3_3") (pintype "passive"))
    )
    (net (code "72") (name "unconnected-(JP2-Pad12)") (class "Default")
      (node (ref "JP2") (pin "12") (pinfunction "12_12") (pintype "passive"))
    )
    (net (code "73") (name "unconnected-(JP2-Pad13)") (class "Default")
      (node (ref "JP2") (pin "13") (pinfunction "13_13") (pintype "passive"))
    )
    (net (code "74") (name "unconnected-(JP2-Pad15)") (class "Default")
      (node (ref "JP2") (pin "15") (pinfunction "15_15") (pintype "passive"))
    )
    (net (code "75") (name "unconnected-(JP2-Pad16)") (class "Default")
      (node (ref "JP2") (pin "16") (pinfunction "16_16") (pintype "passive"))
    )
    (net (code "76") (name "unconnected-(U4-AUX_CL-Pad7)") (class "Default")
      (node (ref "U4") (pin "7") (pinfunction "AUX_CL_7") (pintype "passive"))
    )
    (net (code "77") (name "unconnected-(U4-AUX_DA-Pad21)") (class "Default")
      (node (ref "U4") (pin "21") (pinfunction "AUX_DA_21") (pintype "passive"))
    )
    (net (code "78") (name "unconnected-(U4-NC-Pad2)") (class "Default")
      (node (ref "U4") (pin "2") (pinfunction "NC_2") (pintype "passive"))
    )
    (net (code "79") (name "unconnected-(U4-NC-Pad3)") (class "Default")
      (node (ref "U4") (pin "3") (pinfunction "NC_3") (pintype "passive"))
    )
    (net (code "80") (name "unconnected-(U4-NC-Pad4)") (class "Default")
      (node (ref "U4") (pin "4") (pinfunction "NC_4") (pintype "passive"))
    )
    (net (code "81") (name "unconnected-(U4-NC-Pad5)") (class "Default")
      (node (ref "U4") (pin "5") (pinfunction "NC_5") (pintype "passive"))
    )
    (net (code "82") (name "unconnected-(U4-NC-Pad6)") (class "Default")
      (node (ref "U4") (pin "6") (pinfunction "NC_6") (pintype "passive"))
    )
    (net (code "83") (name "unconnected-(U4-NC-Pad14)") (class "Default")
      (node (ref "U4") (pin "14") (pinfunction "NC_14") (pintype "passive"))
    )
    (net (code "84") (name "unconnected-(U4-NC-Pad15)") (class "Default")
      (node (ref "U4") (pin "15") (pinfunction "NC_15") (pintype "passive"))
    )
    (net (code "85") (name "unconnected-(U4-NC-Pad16)") (class "Default")
      (node (ref "U4") (pin "16") (pinfunction "NC_16") (pintype "passive"))
    )
    (net (code "86") (name "unconnected-(U4-NC-Pad17)") (class "Default")
      (node (ref "U4") (pin "17") (pinfunction "NC_17") (pintype "passive"))
    )
    (net (code "87") (name "unconnected-(U4-RESV-Pad19)") (class "Default")
      (node (ref "U4") (pin "19") (pinfunction "RESV_19") (pintype "passive"))
    )
    (net (code "88") (name "unconnected-(U4-RESV{slash}VDDIO(9250)-Pad1)") (class "Default")
      (node (ref "U4") (pin "1") (pinfunction "RESV/VDDIO(9250)_1") (pintype "passive"))
    )
    (net (code "89") (name "unconnected-(U8-PG-Pad3)") (class "Default")
      (node (ref "U8") (pin "3") (pinfunction "PG_3") (pintype "passive"))
    )
  )
)
